# adapter-56dp30a.net
KiCad netlist of a schematic drawn in EAGLE
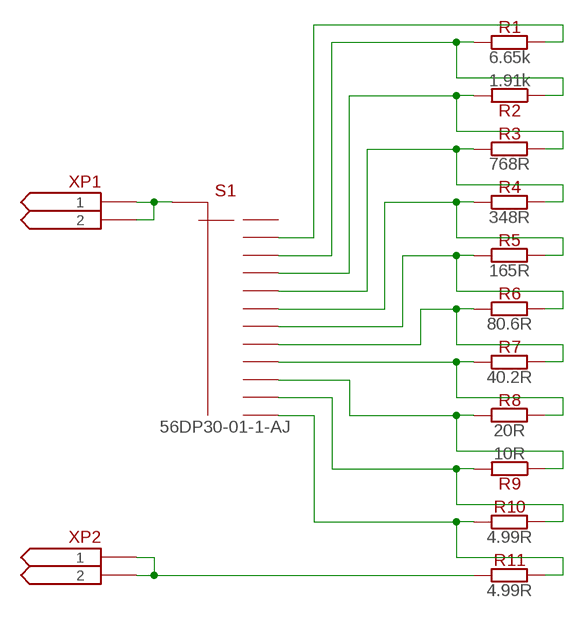
[diagram p0: schematic, sheet 1]

(export (version "E")
  (design (tool "Eeschema 10.0.6"))
  (components
    (comp (ref "R1")
      (value "6.65k")
      (footprint "eagle-import:R-0805")
      (libsource (lib "eagle-import") (part "R-0805"))
    )
    (comp (ref "R2")
      (value "1.91k")
      (footprint "eagle-import:R-0805")
      (libsource (lib "eagle-import") (part "R-0805"))
    )
    (comp (ref "R3")
      (value "768R")
      (footprint "eagle-import:R-0805")
      (libsource (lib "eagle-import") (part "R-0805"))
    )
    (comp (ref "R4")
      (value "348R")
      (footprint "eagle-import:R-0805")
      (libsource (lib "eagle-import") (part "R-0805"))
    )
    (comp (ref "R5")
      (value "165R")
      (footprint "eagle-import:R-0805")
      (libsource (lib "eagle-import") (part "R-0805"))
    )
    (comp (ref "R6")
      (value "80.6R")
      (footprint "eagle-import:R-0805")
      (libsource (lib "eagle-import") (part "R-0805"))
    )
    (comp (ref "R7")
      (value "40.2R")
      (footprint "eagle-import:R-0805")
      (libsource (lib "eagle-import") (part "R-0805"))
    )
    (comp (ref "R8")
      (value "20R")
      (footprint "eagle-import:R-0805")
      (libsource (lib "eagle-import") (part "R-0805"))
    )
    (comp (ref "R9")
      (value "10R")
      (footprint "eagle-import:R-0805")
      (libsource (lib "eagle-import") (part "R-0805"))
    )
    (comp (ref "R10")
      (value "4.99R")
      (footprint "eagle-import:R-0805")
      (libsource (lib "eagle-import") (part "R-0805"))
    )
    (comp (ref "R11")
      (value "4.99R")
      (footprint "eagle-import:R-0805")
      (libsource (lib "eagle-import") (part "R-0805"))
    )
    (comp (ref "S1")
      (value "56DP30-01-1-AJ")
      (footprint "eagle-import:56DP30-01-1")
      (libsource (lib "eagle-import") (part "56DP30-01-1-AJ"))
    )
    (comp (ref "XP1")
      (value "CONN-2-NORMAL")
      (footprint "eagle-import:ML2")
      (libsource (lib "eagle-import") (part "CONN-2-?NORMAL"))
    )
    (comp (ref "XP2")
      (value "CONN-2-NORMAL")
      (footprint "eagle-import:ML2")
      (libsource (lib "eagle-import") (part "CONN-2-?NORMAL"))
    )
  )
  (nets
    (net (code "1") (name "Net-(R1-Pad1)") (class "Default")
      (node (ref "R1") (pin "1") (pinfunction "1_1") (pintype "passive"))
      (node (ref "R2") (pin "1") (pinfunction "1_1") (pintype "passive"))
      (node (ref "S1") (pin "3") (pinfunction "3_3") (pintype "passive"))
    )
    (net (code "2") (name "Net-(R1-Pad2)") (class "Default")
      (node (ref "R1") (pin "2") (pinfunction "2_2") (pintype "passive"))
      (node (ref "S1") (pin "2") (pinfunction "2_2") (pintype "passive"))
    )
    (net (code "3") (name "Net-(R2-Pad2)") (class "Default")
      (node (ref "R2") (pin "2") (pinfunction "2_2") (pintype "passive"))
      (node (ref "R3") (pin "2") (pinfunction "2_2") (pintype "passive"))
      (node (ref "S1") (pin "4") (pinfunction "4_4") (pintype "passive"))
    )
    (net (code "4") (name "Net-(R3-Pad1)") (class "Default")
      (node (ref "R3") (pin "1") (pinfunction "1_1") (pintype "passive"))
      (node (ref "R4") (pin "2") (pinfunction "2_2") (pintype "passive"))
      (node (ref "S1") (pin "5") (pinfunction "5_5") (pintype "passive"))
    )
    (net (code "5") (name "Net-(R4-Pad1)") (class "Default")
      (node (ref "R4") (pin "1") (pinfunction "1_1") (pintype "passive"))
      (node (ref "R5") (pin "2") (pinfunction "2_2") (pintype "passive"))
      (node (ref "S1") (pin "6") (pinfunction "6_6") (pintype "passive"))
    )
    (net (code "6") (name "Net-(R5-Pad1)") (class "Default")
      (node (ref "R5") (pin "1") (pinfunction "1_1") (pintype "passive"))
      (node (ref "R6") (pin "2") (pinfunction "2_2") (pintype "passive"))
      (node (ref "S1") (pin "7") (pinfunction "7_7") (pintype "passive"))
    )
    (net (code "7") (name "Net-(R6-Pad1)") (class "Default")
      (node (ref "R6") (pin "1") (pinfunction "1_1") (pintype "passive"))
      (node (ref "R7") (pin "2") (pinfunction "2_2") (pintype "passive"))
      (node (ref "S1") (pin "8") (pinfunction "8_8") (pintype "passive"))
    )
    (net (code "8") (name "Net-(R7-Pad1)") (class "Default")
      (node (ref "R7") (pin "1") (pinfunction "1_1") (pintype "passive"))
      (node (ref "R8") (pin "2") (pinfunction "2_2") (pintype "passive"))
      (node (ref "S1") (pin "9") (pinfunction "9_9") (pintype "passive"))
    )
    (net (code "9") (name "Net-(R8-Pad1)") (class "Default")
      (node (ref "R8") (pin "1") (pinfunction "1_1") (pintype "passive"))
      (node (ref "R9") (pin "1") (pinfunction "1_1") (pintype "passive"))
      (node (ref "S1") (pin "10") (pinfunction "10_10") (pintype "passive"))
    )
    (net (code "10") (name "Net-(R10-Pad1)") (class "Default")
      (node (ref "R10") (pin "1") (pinfunction "1_1") (pintype "passive"))
      (node (ref "R11") (pin "2") (pinfunction "2_2") (pintype "passive"))
      (node (ref "S1") (pin "12") (pinfunction "12_12") (pintype "passive"))
    )
    (net (code "11") (name "Net-(R10-Pad2)") (class "Default")
      (node (ref "R10") (pin "2") (pinfunction "2_2") (pintype "passive"))
      (node (ref "R9") (pin "2") (pinfunction "2_2") (pintype "passive"))
      (node (ref "S1") (pin "11") (pinfunction "11_11") (pintype "passive"))
    )
    (net (code "12") (name "Net-(R11-Pad1)") (class "Default")
      (node (ref "R11") (pin "1") (pinfunction "1_1") (pintype "passive"))
      (node (ref "XP2") (pin "1") (pinfunction "1_1") (pintype "passive"))
      (node (ref "XP2") (pin "2") (pinfunction "2_2") (pintype "passive"))
    )
    (net (code "13") (name "Net-(S1-CM)") (class "Default")
      (node (ref "S1") (pin "C") (pinfunction "CM_C") (pintype "passive"))
      (node (ref "XP1") (pin "1") (pinfunction "1_1") (pintype "passive"))
      (node (ref "XP1") (pin "2") (pinfunction "2_2") (pintype "passive"))
    )
    (net (code "14") (name "unconnected-(S1-Pad1)") (class "Default")
      (node (ref "S1") (pin "1") (pinfunction "1_1") (pintype "passive"))
    )
  )
)
